# Zio_Qwiic_Air_Quality_Sensor_CCS811.net
KiCad netlist of a schematic drawn in EAGLE
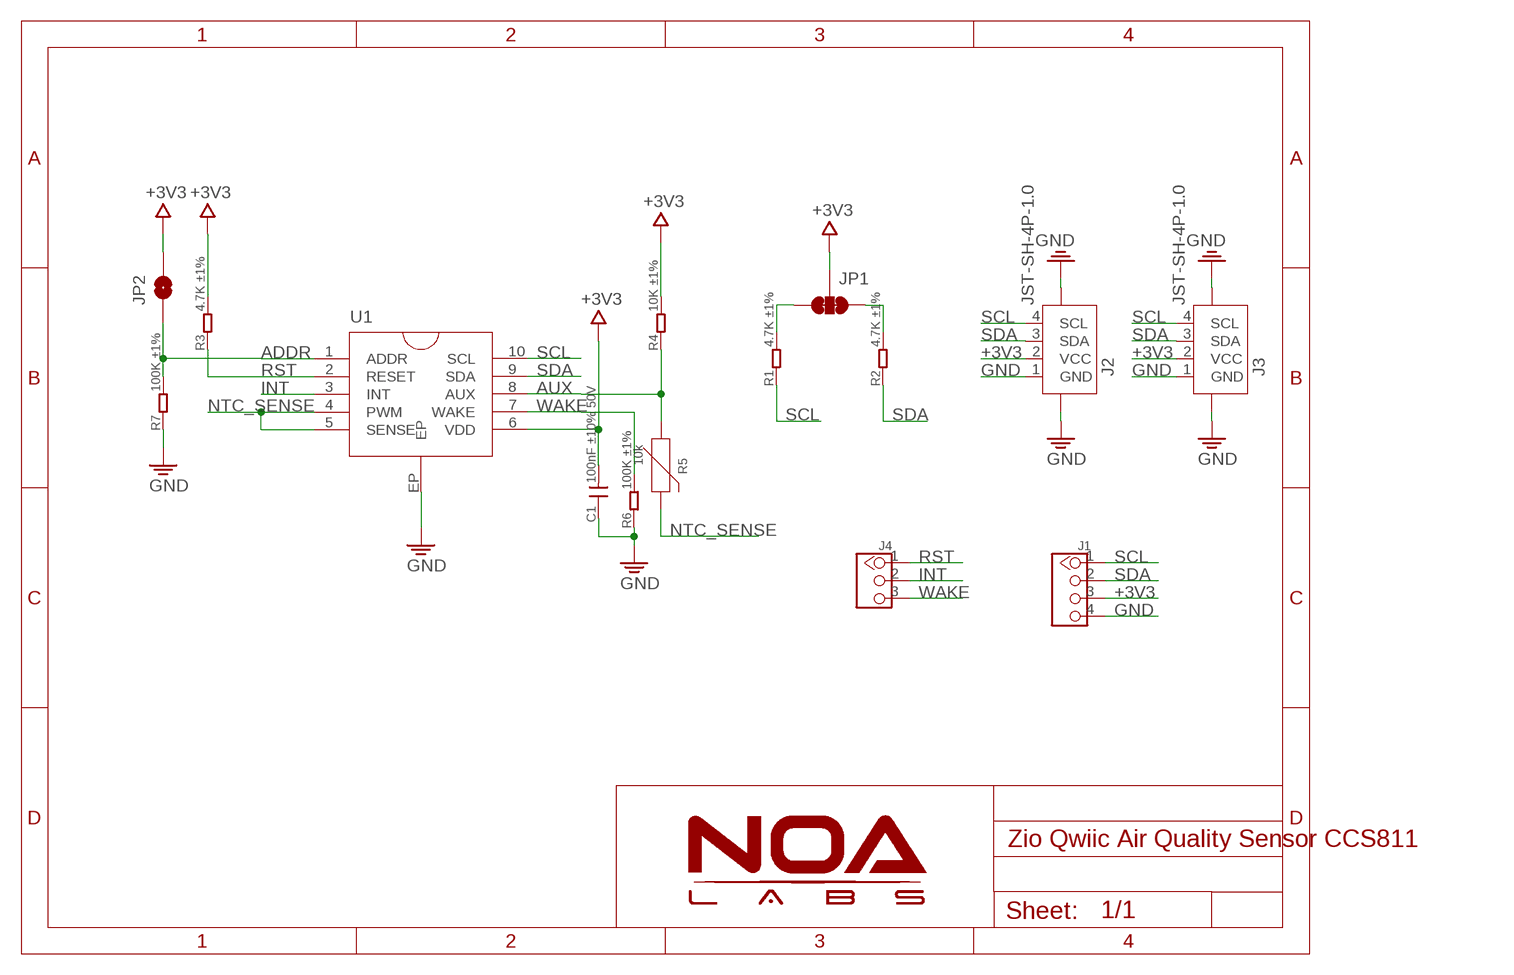
[diagram p0: schematic, sheet 1]

(export (version "E")
  (design (tool "Eeschema 10.0.6"))
  (components
    (comp (ref "C1")
      (value "100nF ±10% 50V")
      (footprint "eagle-import:C0603")
      (libsource (lib "eagle-import") (part "C-0603"))
    )
    (comp (ref "J1")
      (value "HEADER-4P-60/35MIL")
      (footprint "eagle-import:4P-65_35MIL")
      (libsource (lib "eagle-import") (part "HEADER-4P-60/35MIL"))
    )
    (comp (ref "J2")
      (value "JST-SH-4P-1.0")
      (footprint "eagle-import:JST-SH-4P")
      (libsource (lib "eagle-import") (part "JST-SH-4P-1.0"))
    )
    (comp (ref "J3")
      (value "JST-SH-4P-1.0")
      (footprint "eagle-import:JST-SH-4P")
      (libsource (lib "eagle-import") (part "JST-SH-4P-1.0"))
    )
    (comp (ref "J4")
      (value "HEADER-3P-2.54")
      (footprint "eagle-import:3P-2.54")
      (libsource (lib "eagle-import") (part "HEADER-3P-2.54"))
    )
    (comp (ref "JP1")
      (value "SMT-JUMPER_3_2-NC_TRACE")
      (footprint "eagle-import:SMT-JUMPER_3_2-NC_TRACE")
      (libsource (lib "eagle-import") (part "SMT-JUMPER_3_2-NC_TRACE"))
    )
    (comp (ref "JP2")
      (value "JUMPER-SMT_2_NC_PASTE_NOCREM")
      (footprint "eagle-import:SMT-JUMPER_2_NC_PASTE_SILK_NOCREM")
      (libsource (lib "eagle-import") (part "JUMPER-SMT_2_NC_PASTE_NOCREM"))
    )
    (comp (ref "R1")
      (value "4.7K ±1%")
      (footprint "eagle-import:R0603")
      (libsource (lib "eagle-import") (part "R-0603"))
    )
    (comp (ref "R2")
      (value "4.7K ±1%")
      (footprint "eagle-import:R0603")
      (libsource (lib "eagle-import") (part "R-0603"))
    )
    (comp (ref "R3")
      (value "4.7K ±1%")
      (footprint "eagle-import:R0603")
      (libsource (lib "eagle-import") (part "R-0603"))
    )
    (comp (ref "R4")
      (value "10K ±1%")
      (footprint "eagle-import:R0603")
      (libsource (lib "eagle-import") (part "R-0603"))
    )
    (comp (ref "R5")
      (value "10k")
      (footprint "eagle-import:NTC")
      (libsource (lib "eagle-import") (part "R-PHOTOVARISTORNTC"))
    )
    (comp (ref "R6")
      (value "100K ±1%")
      (footprint "eagle-import:R0603")
      (libsource (lib "eagle-import") (part "R-0603"))
    )
    (comp (ref "R7")
      (value "100K ±1%")
      (footprint "eagle-import:R0603")
      (libsource (lib "eagle-import") (part "R-0603"))
    )
    (comp (ref "U1")
      (value "CCS811B")
      (footprint "eagle-import:LGA10")
      (libsource (lib "eagle-import") (part "CCS811B"))
    )
  )
  (nets
    (net (code "1") (name "+3V3") (class "Default")
      (node (ref "C1") (pin "2") (pinfunction "2_2") (pintype "passive"))
      (node (ref "J1") (pin "3") (pinfunction "P$3_3") (pintype "bidirectional"))
      (node (ref "J2") (pin "2") (pinfunction "VCC_2") (pintype "bidirectional"))
      (node (ref "J3") (pin "2") (pinfunction "VCC_2") (pintype "bidirectional"))
      (node (ref "JP1") (pin "2") (pinfunction "2_2") (pintype "passive"))
      (node (ref "JP2") (pin "2") (pinfunction "2_2") (pintype "passive"))
      (node (ref "R3") (pin "2") (pinfunction "2_2") (pintype "passive"))
      (node (ref "R4") (pin "2") (pinfunction "2_2") (pintype "passive"))
      (node (ref "U1") (pin "6") (pinfunction "VDD_6") (pintype "bidirectional"))
    )
    (net (code "2") (name "/ADDR") (class "Default")
      (node (ref "JP2") (pin "1") (pinfunction "1_1") (pintype "passive"))
      (node (ref "R7") (pin "2") (pinfunction "2_2") (pintype "passive"))
      (node (ref "U1") (pin "1") (pinfunction "ADDR_1") (pintype "bidirectional"))
    )
    (net (code "3") (name "/AUX") (class "Default")
      (node (ref "R4") (pin "1") (pinfunction "1_1") (pintype "passive"))
      (node (ref "R5") (pin "2") (pinfunction "P$2_2") (pintype "bidirectional"))
      (node (ref "U1") (pin "8") (pinfunction "AUX_8") (pintype "bidirectional"))
    )
    (net (code "4") (name "/INT") (class "Default")
      (node (ref "J4") (pin "2") (pinfunction "P$2_2") (pintype "bidirectional"))
      (node (ref "U1") (pin "3") (pinfunction "INT_3") (pintype "bidirectional"))
    )
    (net (code "5") (name "/NTC_SENSE") (class "Default")
      (node (ref "R5") (pin "1") (pinfunction "P$1_1") (pintype "bidirectional"))
      (node (ref "U1") (pin "4") (pinfunction "PWM_4") (pintype "bidirectional"))
      (node (ref "U1") (pin "5") (pinfunction "SENSE_5") (pintype "bidirectional"))
    )
    (net (code "6") (name "/RST") (class "Default")
      (node (ref "J4") (pin "1") (pinfunction "P$1_1") (pintype "bidirectional"))
      (node (ref "R3") (pin "1") (pinfunction "1_1") (pintype "passive"))
      (node (ref "U1") (pin "2") (pinfunction "RESET_2") (pintype "bidirectional"))
    )
    (net (code "7") (name "/SCL") (class "Default")
      (node (ref "J1") (pin "1") (pinfunction "P$1_1") (pintype "bidirectional"))
      (node (ref "J2") (pin "4") (pinfunction "SCL_4") (pintype "bidirectional"))
      (node (ref "J3") (pin "4") (pinfunction "SCL_4") (pintype "bidirectional"))
      (node (ref "R1") (pin "1") (pinfunction "1_1") (pintype "passive"))
      (node (ref "U1") (pin "10") (pinfunction "SCL_10") (pintype "bidirectional"))
    )
    (net (code "8") (name "/SDA") (class "Default")
      (node (ref "J1") (pin "2") (pinfunction "P$2_2") (pintype "bidirectional"))
      (node (ref "J2") (pin "3") (pinfunction "SDA_3") (pintype "bidirectional"))
      (node (ref "J3") (pin "3") (pinfunction "SDA_3") (pintype "bidirectional"))
      (node (ref "R2") (pin "1") (pinfunction "1_1") (pintype "passive"))
      (node (ref "U1") (pin "9") (pinfunction "SDA_9") (pintype "bidirectional"))
    )
    (net (code "9") (name "/WAKE") (class "Default")
      (node (ref "J4") (pin "3") (pinfunction "P$3_3") (pintype "bidirectional"))
      (node (ref "R6") (pin "2") (pinfunction "2_2") (pintype "passive"))
      (node (ref "U1") (pin "7") (pinfunction "WAKE_7") (pintype "bidirectional"))
    )
    (net (code "10") (name "GND") (class "Default")
      (node (ref "C1") (pin "1") (pinfunction "1_1") (pintype "passive"))
      (node (ref "J1") (pin "4") (pinfunction "P$4_4") (pintype "bidirectional"))
      (node (ref "J2") (pin "1") (pinfunction "GND_1") (pintype "bidirectional"))
      (node (ref "J2") (pin "NC1") (pinfunction "5_NC1") (pintype "bidirectional"))
      (node (ref "J2") (pin "NC2") (pinfunction "6_NC2") (pintype "bidirectional"))
      (node (ref "J3") (pin "1") (pinfunction "GND_1") (pintype "bidirectional"))
      (node (ref "J3") (pin "NC1") (pinfunction "5_NC1") (pintype "bidirectional"))
      (node (ref "J3") (pin "NC2") (pinfunction "6_NC2") (pintype "bidirectional"))
      (node (ref "R6") (pin "1") (pinfunction "1_1") (pintype "passive"))
      (node (ref "R7") (pin "1") (pinfunction "1_1") (pintype "passive"))
      (node (ref "U1") (pin "EP") (pinfunction "EP_EP") (pintype "bidirectional"))
    )
    (net (code "11") (name "Net-(JP1-Pad1)") (class "Default")
      (node (ref "JP1") (pin "1") (pinfunction "1_1") (pintype "passive"))
      (node (ref "R2") (pin "2") (pinfunction "2_2") (pintype "passive"))
    )
    (net (code "12") (name "Net-(JP1-Pad3)") (class "Default")
      (node (ref "JP1") (pin "3") (pinfunction "3_3") (pintype "passive"))
      (node (ref "R1") (pin "2") (pinfunction "2_2") (pintype "passive"))
    )
  )
)
